# p7_1_3v3.net
KiCad netlist of a schematic drawn in EAGLE
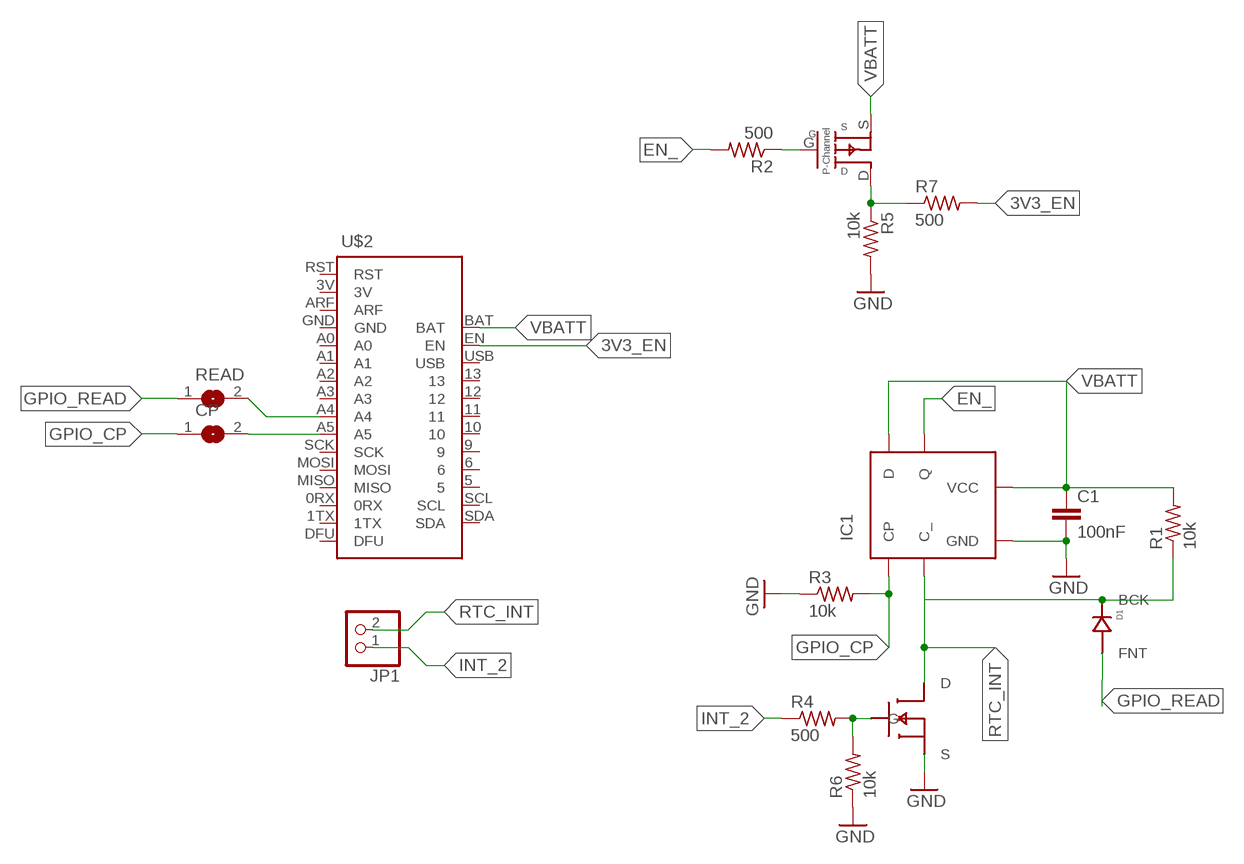
[diagram p0: schematic, sheet 1]

(export (version "E")
  (design (tool "Eeschema 10.0.6"))
  (components
    (comp (ref "C1")
      (value "100nF")
      (footprint "eagle-import:C0805")
      (libsource (lib "eagle-import") (part "C"))
    )
    (comp (ref "CP") (value "SJ") (footprint "eagle-import:SJ") (libsource (lib "eagle-import") (part "SJ")))
    (comp (ref "D1")
      (value "DIODE-DO-214AC")
      (footprint "eagle-import:DIODE-DO-214AC")
      (libsource (lib "eagle-import") (part "DIODE-DO-214AC"))
    )
    (comp (ref "IC1")
      (value "NC7SZ175")
      (footprint "eagle-import:SC70")
      (libsource (lib "eagle-import") (part "NC7SZ175"))
    )
    (comp (ref "JP1")
      (value "PINHD-1X2")
      (footprint "eagle-import:1X02")
      (libsource (lib "eagle-import") (part "PINHD-1X2"))
    )
    (comp (ref "Q1")
      (value "MOSFET-SOT23F")
      (footprint "eagle-import:SOT-23F")
      (libsource (lib "eagle-import") (part "MOSFET-SOT23F"))
    )
    (comp (ref "Q2")
      (value "SSM3J3228R")
      (footprint "eagle-import:SOT-23-3")
      (libsource (lib "eagle-import") (part "SSM3J3228R"))
    )
    (comp (ref "R1")
      (value "10k")
      (footprint "eagle-import:R0805")
      (libsource (lib "eagle-import") (part "R-US_R0805"))
    )
    (comp (ref "R2")
      (value "500")
      (footprint "eagle-import:R0805")
      (libsource (lib "eagle-import") (part "R-US_R0805"))
    )
    (comp (ref "R3")
      (value "10k")
      (footprint "eagle-import:R0805")
      (libsource (lib "eagle-import") (part "R-US_R0805"))
    )
    (comp (ref "R4")
      (value "500")
      (footprint "eagle-import:R0805")
      (libsource (lib "eagle-import") (part "R-US_R0805"))
    )
    (comp (ref "R5")
      (value "10k")
      (footprint "eagle-import:R0805")
      (libsource (lib "eagle-import") (part "R-US_R0805"))
    )
    (comp (ref "R6")
      (value "10k")
      (footprint "eagle-import:R0805")
      (libsource (lib "eagle-import") (part "R-US_R0805"))
    )
    (comp (ref "R7")
      (value "500")
      (footprint "eagle-import:R0805")
      (libsource (lib "eagle-import") (part "R-US_R0805"))
    )
    (comp (ref "READ")
      (value "SJ")
      (footprint "eagle-import:SJ")
      (libsource (lib "eagle-import") (part "SJ"))
    )
    (comp (ref "U$2")
      (value "BLUEFRUIT_M0")
      (footprint "eagle-import:BLUEFRUIT_MO")
      (libsource (lib "eagle-import") (part "BLUEFRUIT_M0"))
    )
  )
  (nets
    (net (code "1") (name "3V3_EN") (class "Default")
      (node (ref "R7") (pin "2") (pinfunction "2_2") (pintype "passive"))
      (node (ref "U$2") (pin "EN") (pinfunction "EN_EN") (pintype "bidirectional"))
    )
    (net (code "2") (name "EN_") (class "Default")
      (node (ref "IC1") (pin "Q") (pinfunction "Q_Q") (pintype "bidirectional"))
      (node (ref "R2") (pin "2") (pinfunction "2_2") (pintype "passive"))
    )
    (net (code "3") (name "GND") (class "Default")
      (node (ref "C1") (pin "2") (pinfunction "2_2") (pintype "passive"))
      (node (ref "IC1") (pin "GND") (pinfunction "GND_GND") (pintype "bidirectional"))
      (node (ref "Q1") (pin "S") (pinfunction "S_S") (pintype "bidirectional"))
      (node (ref "R3") (pin "1") (pinfunction "1_1") (pintype "passive"))
      (node (ref "R5") (pin "2") (pinfunction "2_2") (pintype "passive"))
      (node (ref "R6") (pin "1") (pinfunction "1_1") (pintype "passive"))
    )
    (net (code "4") (name "GPIO_CP") (class "Default")
      (node (ref "CP") (pin "1") (pinfunction "1_1") (pintype "passive"))
      (node (ref "IC1") (pin "CP") (pinfunction "CP_CP") (pintype "bidirectional"))
      (node (ref "R3") (pin "2") (pinfunction "2_2") (pintype "passive"))
    )
    (net (code "5") (name "GPIO_READ") (class "Default")
      (node (ref "D1") (pin "FNT") (pinfunction "FNT_FNT") (pintype "bidirectional"))
      (node (ref "READ") (pin "1") (pinfunction "1_1") (pintype "passive"))
    )
    (net (code "6") (name "INT_2") (class "Default")
      (node (ref "JP1") (pin "1") (pinfunction "1_1") (pintype "passive"))
      (node (ref "R4") (pin "1") (pinfunction "1_1") (pintype "passive"))
    )
    (net (code "7") (name "Net-(CP-Pad2)") (class "Default")
      (node (ref "CP") (pin "2") (pinfunction "2_2") (pintype "passive"))
      (node (ref "U$2") (pin "A5") (pinfunction "A5_A5") (pintype "bidirectional"))
    )
    (net (code "8") (name "Net-(Q1-PadG)") (class "Default")
      (node (ref "Q1") (pin "G") (pinfunction "G_G") (pintype "bidirectional"))
      (node (ref "R4") (pin "2") (pinfunction "2_2") (pintype "passive"))
      (node (ref "R6") (pin "2") (pinfunction "2_2") (pintype "passive"))
    )
    (net (code "9") (name "Net-(Q2-PadD)") (class "Default")
      (node (ref "Q2") (pin "D") (pinfunction "D_D") (pintype "bidirectional"))
      (node (ref "R5") (pin "1") (pinfunction "1_1") (pintype "passive"))
      (node (ref "R7") (pin "1") (pinfunction "1_1") (pintype "passive"))
    )
    (net (code "10") (name "Net-(Q2-PadG)") (class "Default")
      (node (ref "Q2") (pin "G") (pinfunction "G_G") (pintype "bidirectional"))
      (node (ref "R2") (pin "1") (pinfunction "1_1") (pintype "passive"))
    )
    (net (code "11") (name "Net-(READ-Pad2)") (class "Default")
      (node (ref "READ") (pin "2") (pinfunction "2_2") (pintype "passive"))
      (node (ref "U$2") (pin "A4") (pinfunction "A4_A4") (pintype "bidirectional"))
    )
    (net (code "12") (name "RTC_INT") (class "Default")
      (node (ref "D1") (pin "BCK") (pinfunction "BCK_BCK") (pintype "bidirectional"))
      (node (ref "IC1") (pin "C_") (pinfunction "C__C_") (pintype "bidirectional"))
      (node (ref "JP1") (pin "2") (pinfunction "2_2") (pintype "passive"))
      (node (ref "Q1") (pin "D") (pinfunction "D_D") (pintype "bidirectional"))
      (node (ref "R1") (pin "1") (pinfunction "1_1") (pintype "passive"))
    )
    (net (code "13") (name "VBATT") (class "Default")
      (node (ref "C1") (pin "1") (pinfunction "1_1") (pintype "passive"))
      (node (ref "IC1") (pin "D") (pinfunction "D_D") (pintype "bidirectional"))
      (node (ref "IC1") (pin "VCC") (pinfunction "VCC_VCC") (pintype "bidirectional"))
      (node (ref "Q2") (pin "S") (pinfunction "S_S") (pintype "bidirectional"))
      (node (ref "R1") (pin "2") (pinfunction "2_2") (pintype "passive"))
      (node (ref "U$2") (pin "BAT") (pinfunction "BAT_BAT") (pintype "bidirectional"))
    )
    (net (code "14") (name "unconnected-(U$2-Pad0RX)") (class "Default")
      (node (ref "U$2") (pin "0RX") (pinfunction "0RX_0RX") (pintype "bidirectional"))
    )
    (net (code "15") (name "unconnected-(U$2-Pad1TX)") (class "Default")
      (node (ref "U$2") (pin "1TX") (pinfunction "1TX_1TX") (pintype "bidirectional"))
    )
    (net (code "16") (name "unconnected-(U$2-Pad3V)") (class "Default")
      (node (ref "U$2") (pin "3V") (pinfunction "3V_3V") (pintype "bidirectional"))
    )
    (net (code "17") (name "unconnected-(U$2-Pad5)") (class "Default")
      (node (ref "U$2") (pin "5") (pinfunction "5_5") (pintype "bidirectional"))
    )
    (net (code "18") (name "unconnected-(U$2-Pad6)") (class "Default")
      (node (ref "U$2") (pin "6") (pinfunction "6_6") (pintype "bidirectional"))
    )
    (net (code "19") (name "unconnected-(U$2-Pad9)") (class "Default")
      (node (ref "U$2") (pin "9") (pinfunction "9_9") (pintype "bidirectional"))
    )
    (net (code "20") (name "unconnected-(U$2-Pad10)") (class "Default")
      (node (ref "U$2") (pin "10") (pinfunction "10_10") (pintype "bidirectional"))
    )
    (net (code "21") (name "unconnected-(U$2-Pad11)") (class "Default")
      (node (ref "U$2") (pin "11") (pinfunction "11_11") (pintype "bidirectional"))
    )
    (net (code "22") (name "unconnected-(U$2-Pad12)") (class "Default")
      (node (ref "U$2") (pin "12") (pinfunction "12_12") (pintype "bidirectional"))
    )
    (net (code "23") (name "unconnected-(U$2-Pad13)") (class "Default")
      (node (ref "U$2") (pin "13") (pinfunction "13_13") (pintype "bidirectional"))
    )
    (net (code "24") (name "unconnected-(U$2-PadA0)") (class "Default")
      (node (ref "U$2") (pin "A0") (pinfunction "A0_A0") (pintype "bidirectional"))
    )
    (net (code "25") (name "unconnected-(U$2-PadA1)") (class "Default")
      (node (ref "U$2") (pin "A1") (pinfunction "A1_A1") (pintype "bidirectional"))
    )
    (net (code "26") (name "unconnected-(U$2-PadA2)") (class "Default")
      (node (ref "U$2") (pin "A2") (pinfunction "A2_A2") (pintype "bidirectional"))
    )
    (net (code "27") (name "unconnected-(U$2-PadA3)") (class "Default")
      (node (ref "U$2") (pin "A3") (pinfunction "A3_A3") (pintype "bidirectional"))
    )
    (net (code "28") (name "unconnected-(U$2-PadARF)") (class "Default")
      (node (ref "U$2") (pin "ARF") (pinfunction "ARF_ARF") (pintype "bidirectional"))
    )
    (net (code "29") (name "unconnected-(U$2-PadDFU)") (class "Default")
      (node (ref "U$2") (pin "DFU") (pinfunction "DFU_DFU") (pintype "bidirectional"))
    )
    (net (code "30") (name "unconnected-(U$2-PadGND)") (class "Default")
      (node (ref "U$2") (pin "GND") (pinfunction "GND_GND") (pintype "bidirectional"))
    )
    (net (code "31") (name "unconnected-(U$2-PadMISO)") (class "Default")
      (node (ref "U$2") (pin "MISO") (pinfunction "MISO_MISO") (pintype "bidirectional"))
    )
    (net (code "32") (name "unconnected-(U$2-PadMOSI)") (class "Default")
      (node (ref "U$2") (pin "MOSI") (pinfunction "MOSI_MOSI") (pintype "bidirectional"))
    )
    (net (code "33") (name "unconnected-(U$2-PadRST)") (class "Default")
      (node (ref "U$2") (pin "RST") (pinfunction "RST_RST") (pintype "bidirectional"))
    )
    (net (code "34") (name "unconnected-(U$2-PadSCK)") (class "Default")
      (node (ref "U$2") (pin "SCK") (pinfunction "SCK_SCK") (pintype "bidirectional"))
    )
    (net (code "35") (name "unconnected-(U$2-PadSCL)") (class "Default")
      (node (ref "U$2") (pin "SCL") (pinfunction "SCL_SCL") (pintype "bidirectional"))
    )
    (net (code "36") (name "unconnected-(U$2-PadSDA)") (class "Default")
      (node (ref "U$2") (pin "SDA") (pinfunction "SDA_SDA") (pintype "bidirectional"))
    )
    (net (code "37") (name "unconnected-(U$2-PadUSB)") (class "Default")
      (node (ref "U$2") (pin "USB") (pinfunction "USB_USB") (pintype "bidirectional"))
    )
  )
)
